# ESP_toster_2021-06-03.net
KiCad netlist of a schematic drawn in EasyEDA
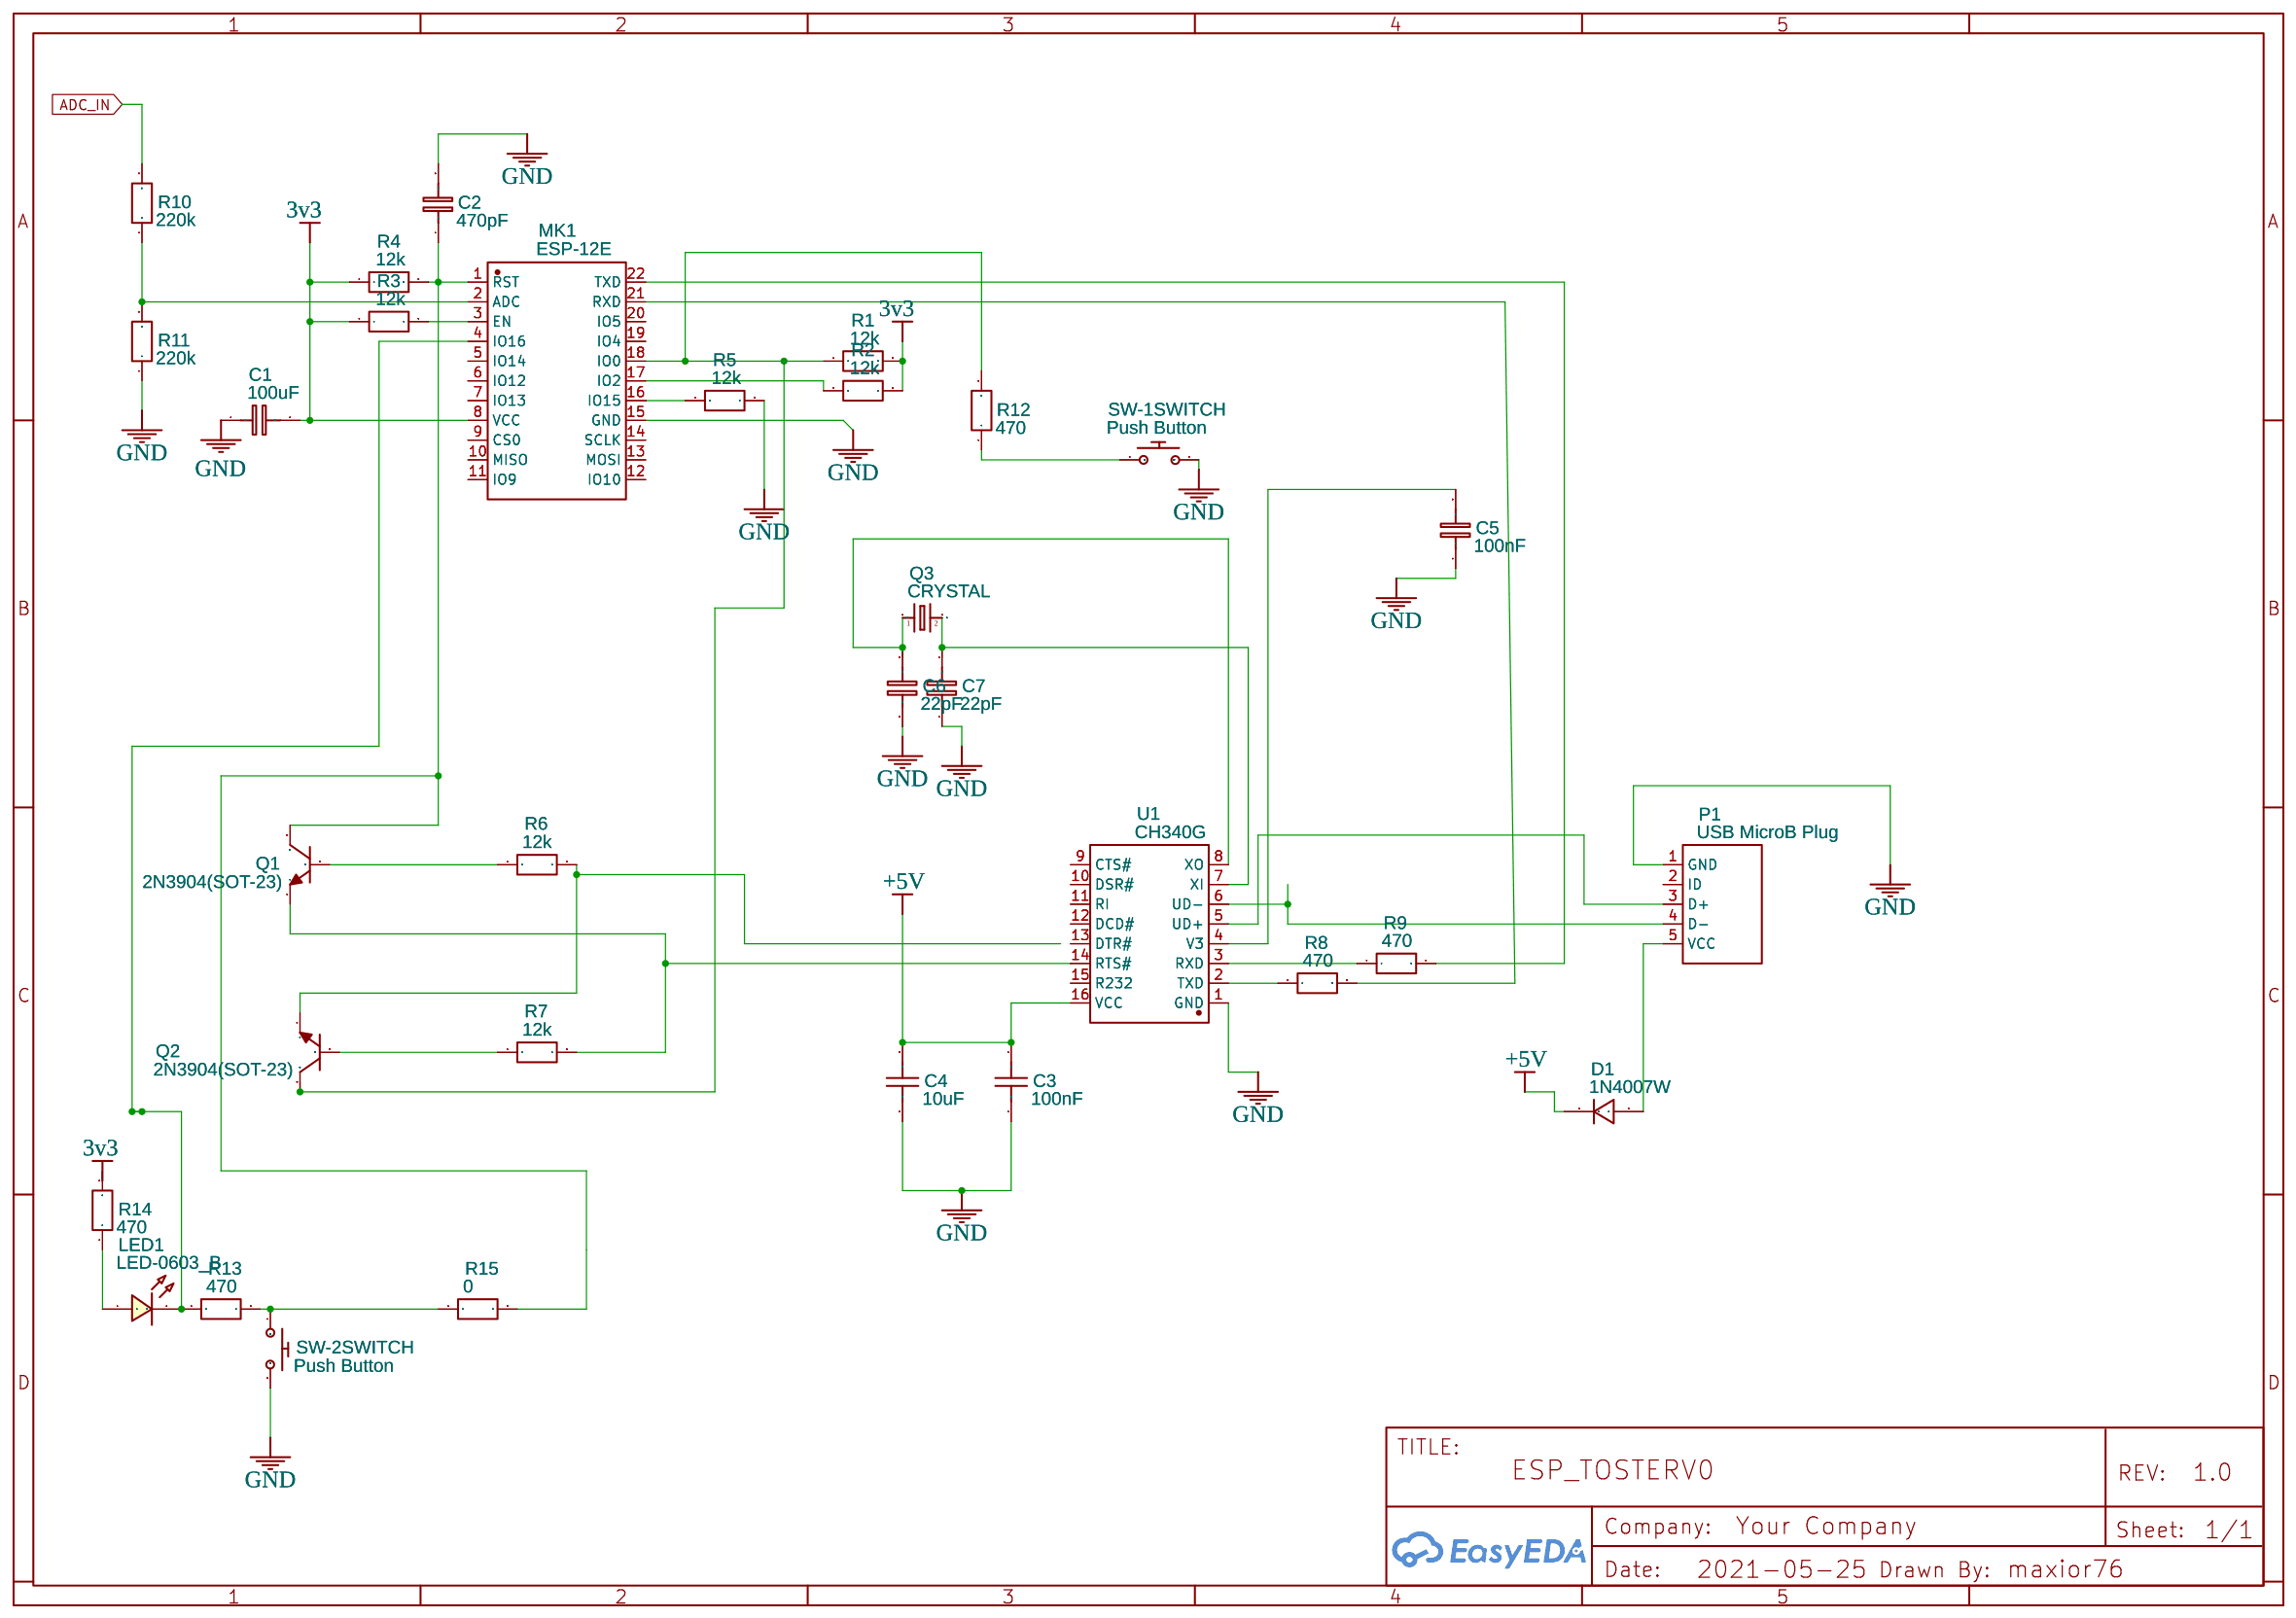
[diagram p0: schematic sheet]

(export (version "E")
  (design (tool "Eeschema 10.0.6"))
  (components
    (comp (ref "C1") (value "100uF") (libsource (lib "") (part "C_0603_EU")))
    (comp (ref "C2") (value "470pF") (libsource (lib "") (part "C_0603_EU_3")))
    (comp (ref "C3") (value "100nF") (libsource (lib "") (part "C_0603_US")))
    (comp (ref "C4") (value "10uF") (libsource (lib "") (part "C_0603_US")))
    (comp (ref "C5") (value "100nF") (libsource (lib "") (part "C_0603_EU_1")))
    (comp (ref "C6") (value "22pF") (libsource (lib "") (part "C_0603_EU_2")))
    (comp (ref "C7") (value "22pF") (libsource (lib "") (part "C_0603_EU_2")))
    (comp (ref "D1")
      (value "1N4007W")
      (fields (field (name "BOM_Supplier Part") "C328592"))
      (libsource (lib "") (part "1N4007W"))
    )
    (comp (ref "LED1")
      (value "LED-0603_B")
      (fields
        (field (name "BOM_Manufacturer Part") "19-217/R6C-AL1M2VY/3T")
        (field (name "BOM_Supplier Part") "C72044")
      )
      (libsource (lib "") (part "LED-0603_R"))
    )
    (comp (ref "MK1")
      (value "ESP-12E")
      (fields (field (name "BOM_Supplier Part") "C89297"))
      (libsource (lib "") (part "ESP-12E"))
    )
    (comp (ref "P1") (value "USB MicroB Plug") (libsource (lib "") (part "USB MicroB Plug")))
    (comp (ref "Q1")
      (value "2N3904(SOT-23)")
      (fields
        (field (name "BOM_Manufacturer Part") "2n3904S-RTK/PS")
        (field (name "BOM_Supplier Part") "C18536")
      )
      (libsource (lib "") (part "2N3904(SOT-23)_1"))
    )
    (comp (ref "Q2")
      (value "2N3904(SOT-23)")
      (fields
        (field (name "BOM_Manufacturer Part") "2n3904S-RTK/PS")
        (field (name "BOM_Supplier Part") "C18536")
      )
      (libsource (lib "") (part "2N3904(SOT-23)"))
    )
    (comp (ref "Q3") (value "CRYSTAL") (libsource (lib "") (part "CRYSTAL")))
    (comp (ref "R1") (value "12k") (libsource (lib "") (part "R_0603_EU")))
    (comp (ref "R2") (value "12k") (libsource (lib "") (part "R_0603_EU")))
    (comp (ref "R3") (value "12k") (libsource (lib "") (part "R_0603_EU")))
    (comp (ref "R4") (value "12k") (libsource (lib "") (part "R_0603_EU")))
    (comp (ref "R5") (value "12k") (libsource (lib "") (part "R_0603_EU")))
    (comp (ref "R6") (value "12k") (libsource (lib "") (part "R_0603_EU")))
    (comp (ref "R7") (value "12k") (libsource (lib "") (part "R_0603_EU")))
    (comp (ref "R8") (value "470") (libsource (lib "") (part "R_0603_EU")))
    (comp (ref "R9") (value "470") (libsource (lib "") (part "R_0603_EU")))
    (comp (ref "R10") (value "220k") (libsource (lib "") (part "R_0603_EU_1")))
    (comp (ref "R11") (value "220k") (libsource (lib "") (part "R_0603_EU_1")))
    (comp (ref "R12") (value "470") (libsource (lib "") (part "R_0603_EU_1")))
    (comp (ref "R13") (value "470") (libsource (lib "") (part "R_0603_EU")))
    (comp (ref "R14") (value "470") (libsource (lib "") (part "R_0603_EU_1")))
    (comp (ref "R15") (value "0") (libsource (lib "") (part "R_0603_EU")))
    (comp (ref "SW-1SWITCH")
      (value "Push Button")
      (fields (field (name "BOM_Supplier Part") "COM-08720"))
      (libsource (lib "") (part "Push Button_1"))
    )
    (comp (ref "SW-2SWITCH")
      (value "Push Button")
      (fields (field (name "BOM_Supplier Part") "COM-08720"))
      (libsource (lib "") (part "Push Button"))
    )
    (comp (ref "U1")
      (value "CH340G")
      (fields (field (name "BOM_Supplier Part") "C14267"))
      (libsource (lib "") (part "CH340G"))
    )
  )
  (nets
    (net (code "1") (name "+5V") (class "Default")
      (node (ref "C3") (pin "2") (pinfunction "2_2") (pintype "unspecified"))
      (node (ref "C4") (pin "2") (pinfunction "2_2") (pintype "unspecified"))
      (node (ref "D1") (pin "1") (pinfunction "1_1") (pintype "unspecified"))
      (node (ref "U1") (pin "16") (pinfunction "VCC_16") (pintype "unspecified"))
    )
    (net (code "2") (name "3v3") (class "Default")
      (node (ref "C1") (pin "2") (pinfunction "2_2") (pintype "unspecified"))
      (node (ref "MK1") (pin "8") (pinfunction "VCC_8") (pintype "unspecified"))
      (node (ref "R1") (pin "2") (pinfunction "2_2") (pintype "unspecified"))
      (node (ref "R14") (pin "2") (pinfunction "2_2") (pintype "unspecified"))
      (node (ref "R2") (pin "2") (pinfunction "2_2") (pintype "unspecified"))
      (node (ref "R3") (pin "1") (pinfunction "1_1") (pintype "unspecified"))
      (node (ref "R4") (pin "1") (pinfunction "1_1") (pintype "unspecified"))
    )
    (net (code "3") (name "ADC_IN") (class "Default")
      (node (ref "R10") (pin "2") (pinfunction "2_2") (pintype "unspecified"))
    )
    (net (code "4") (name "GND") (class "Default")
      (node (ref "C1") (pin "1") (pinfunction "1_1") (pintype "unspecified"))
      (node (ref "C2") (pin "2") (pinfunction "2_2") (pintype "unspecified"))
      (node (ref "C3") (pin "1") (pinfunction "1_1") (pintype "unspecified"))
      (node (ref "C4") (pin "1") (pinfunction "1_1") (pintype "unspecified"))
      (node (ref "C5") (pin "1") (pinfunction "1_1") (pintype "unspecified"))
      (node (ref "C6") (pin "1") (pinfunction "1_1") (pintype "unspecified"))
      (node (ref "C7") (pin "1") (pinfunction "1_1") (pintype "unspecified"))
      (node (ref "MK1") (pin "15") (pinfunction "GND_15") (pintype "unspecified"))
      (node (ref "P1") (pin "1") (pinfunction "GND_1") (pintype "unspecified"))
      (node (ref "R11") (pin "1") (pinfunction "1_1") (pintype "unspecified"))
      (node (ref "R5") (pin "2") (pinfunction "2_2") (pintype "unspecified"))
      (node (ref "SW-1SWITCH") (pin "2") (pinfunction "P$2_2") (pintype "unspecified"))
      (node (ref "SW-2SWITCH") (pin "2") (pinfunction "P$2_2") (pintype "unspecified"))
      (node (ref "U1") (pin "1") (pinfunction "GND_1") (pintype "unspecified"))
    )
    (net (code "5") (name "Net-(LED1-Pad1)") (class "Default")
      (node (ref "LED1") (pin "1") (pinfunction "1_1") (pintype "unspecified"))
      (node (ref "R14") (pin "1") (pinfunction "1_1") (pintype "unspecified"))
    )
    (net (code "6") (name "Net-(MK1-ADC)") (class "Default")
      (node (ref "MK1") (pin "2") (pinfunction "ADC_2") (pintype "unspecified"))
      (node (ref "R10") (pin "1") (pinfunction "1_1") (pintype "unspecified"))
      (node (ref "R11") (pin "2") (pinfunction "2_2") (pintype "unspecified"))
    )
    (net (code "7") (name "Net-(MK1-EN)") (class "Default")
      (node (ref "MK1") (pin "3") (pinfunction "EN_3") (pintype "unspecified"))
      (node (ref "R3") (pin "2") (pinfunction "2_2") (pintype "unspecified"))
    )
    (net (code "8") (name "Net-(MK1-IO0)") (class "Default")
      (node (ref "MK1") (pin "18") (pinfunction "IO0_18") (pintype "unspecified"))
      (node (ref "Q2") (pin "3") (pinfunction "C_3") (pintype "input"))
      (node (ref "R1") (pin "1") (pinfunction "1_1") (pintype "unspecified"))
      (node (ref "R12") (pin "2") (pinfunction "2_2") (pintype "unspecified"))
    )
    (net (code "9") (name "Net-(MK1-IO2)") (class "Default")
      (node (ref "MK1") (pin "17") (pinfunction "IO2_17") (pintype "unspecified"))
      (node (ref "R2") (pin "1") (pinfunction "1_1") (pintype "unspecified"))
    )
    (net (code "10") (name "Net-(MK1-IO15)") (class "Default")
      (node (ref "MK1") (pin "16") (pinfunction "IO15_16") (pintype "unspecified"))
      (node (ref "R5") (pin "1") (pinfunction "1_1") (pintype "unspecified"))
    )
    (net (code "11") (name "Net-(MK1-IO16)") (class "Default")
      (node (ref "LED1") (pin "2") (pinfunction "2_2") (pintype "unspecified"))
      (node (ref "MK1") (pin "4") (pinfunction "IO16_4") (pintype "unspecified"))
      (node (ref "R13") (pin "1") (pinfunction "1_1") (pintype "unspecified"))
    )
    (net (code "12") (name "Net-(MK1-RST)") (class "Default")
      (node (ref "C2") (pin "1") (pinfunction "1_1") (pintype "unspecified"))
      (node (ref "MK1") (pin "1") (pinfunction "RST_1") (pintype "unspecified"))
      (node (ref "Q1") (pin "3") (pinfunction "C_3") (pintype "input"))
      (node (ref "R15") (pin "2") (pinfunction "2_2") (pintype "unspecified"))
      (node (ref "R4") (pin "2") (pinfunction "2_2") (pintype "unspecified"))
    )
    (net (code "13") (name "Net-(MK1-RXD)") (class "Default")
      (node (ref "MK1") (pin "21") (pinfunction "RXD_21") (pintype "unspecified"))
      (node (ref "R8") (pin "2") (pinfunction "2_2") (pintype "unspecified"))
    )
    (net (code "14") (name "Net-(MK1-TXD)") (class "Default")
      (node (ref "MK1") (pin "22") (pinfunction "TXD_22") (pintype "unspecified"))
      (node (ref "R9") (pin "2") (pinfunction "2_2") (pintype "unspecified"))
    )
    (net (code "15") (name "Net-(P1-D+)") (class "Default")
      (node (ref "P1") (pin "3") (pinfunction "D+_3") (pintype "unspecified"))
      (node (ref "U1") (pin "5") (pinfunction "UD+_5") (pintype "unspecified"))
    )
    (net (code "16") (name "Net-(P1-D-)") (class "Default")
      (node (ref "P1") (pin "4") (pinfunction "D-_4") (pintype "unspecified"))
      (node (ref "U1") (pin "6") (pinfunction "UD-_6") (pintype "unspecified"))
    )
    (net (code "17") (name "Net-(P1-VCC)") (class "Default")
      (node (ref "D1") (pin "2") (pinfunction "2_2") (pintype "unspecified"))
      (node (ref "P1") (pin "5") (pinfunction "VCC_5") (pintype "unspecified"))
    )
    (net (code "18") (name "Net-(Q1-B)") (class "Default")
      (node (ref "Q1") (pin "2") (pinfunction "B_2") (pintype "input"))
      (node (ref "R6") (pin "1") (pinfunction "1_1") (pintype "unspecified"))
    )
    (net (code "19") (name "Net-(Q1-E)") (class "Default")
      (node (ref "Q1") (pin "1") (pinfunction "E_1") (pintype "input"))
      (node (ref "R7") (pin "2") (pinfunction "2_2") (pintype "unspecified"))
      (node (ref "U1") (pin "14") (pinfunction "RTS#_14") (pintype "unspecified"))
    )
    (net (code "20") (name "Net-(Q2-B)") (class "Default")
      (node (ref "Q2") (pin "2") (pinfunction "B_2") (pintype "input"))
      (node (ref "R7") (pin "1") (pinfunction "1_1") (pintype "unspecified"))
    )
    (net (code "21") (name "Net-(Q2-E)") (class "Default")
      (node (ref "Q2") (pin "1") (pinfunction "E_1") (pintype "input"))
      (node (ref "R6") (pin "2") (pinfunction "2_2") (pintype "unspecified"))
    )
    (net (code "22") (name "Net-(SW-1SWITCH-P$1)") (class "Default")
      (node (ref "R12") (pin "1") (pinfunction "1_1") (pintype "unspecified"))
      (node (ref "SW-1SWITCH") (pin "1") (pinfunction "P$1_1") (pintype "unspecified"))
    )
    (net (code "23") (name "Net-(SW-2SWITCH-P$1)") (class "Default")
      (node (ref "R13") (pin "2") (pinfunction "2_2") (pintype "unspecified"))
      (node (ref "R15") (pin "1") (pinfunction "1_1") (pintype "unspecified"))
      (node (ref "SW-2SWITCH") (pin "1") (pinfunction "P$1_1") (pintype "unspecified"))
    )
    (net (code "24") (name "Net-(U1-RXD)") (class "Default")
      (node (ref "R9") (pin "1") (pinfunction "1_1") (pintype "unspecified"))
      (node (ref "U1") (pin "3") (pinfunction "RXD_3") (pintype "unspecified"))
    )
    (net (code "25") (name "Net-(U1-TXD)") (class "Default")
      (node (ref "R8") (pin "1") (pinfunction "1_1") (pintype "unspecified"))
      (node (ref "U1") (pin "2") (pinfunction "TXD_2") (pintype "unspecified"))
    )
    (net (code "26") (name "Net-(U1-V3)") (class "Default")
      (node (ref "C5") (pin "2") (pinfunction "2_2") (pintype "unspecified"))
      (node (ref "U1") (pin "4") (pinfunction "V3_4") (pintype "unspecified"))
    )
    (net (code "27") (name "Net-(U1-XI)") (class "Default")
      (node (ref "C7") (pin "2") (pinfunction "2_2") (pintype "unspecified"))
      (node (ref "Q3") (pin "2") (pinfunction "2_2") (pintype "unspecified"))
      (node (ref "U1") (pin "7") (pinfunction "XI_7") (pintype "unspecified"))
    )
    (net (code "28") (name "Net-(U1-XO)") (class "Default")
      (node (ref "C6") (pin "2") (pinfunction "2_2") (pintype "unspecified"))
      (node (ref "Q3") (pin "1") (pinfunction "1_1") (pintype "unspecified"))
      (node (ref "U1") (pin "8") (pinfunction "XO_8") (pintype "unspecified"))
    )
    (net (code "29") (name "unconnected-(MK1-CS0-Pad9)") (class "Default")
      (node (ref "MK1") (pin "9") (pinfunction "CS0_9") (pintype "unspecified"))
    )
    (net (code "30") (name "unconnected-(MK1-IO4-Pad19)") (class "Default")
      (node (ref "MK1") (pin "19") (pinfunction "IO4_19") (pintype "unspecified"))
    )
    (net (code "31") (name "unconnected-(MK1-IO5-Pad20)") (class "Default")
      (node (ref "MK1") (pin "20") (pinfunction "IO5_20") (pintype "unspecified"))
    )
    (net (code "32") (name "unconnected-(MK1-IO9-Pad11)") (class "Default")
      (node (ref "MK1") (pin "11") (pinfunction "IO9_11") (pintype "unspecified"))
    )
    (net (code "33") (name "unconnected-(MK1-IO10-Pad12)") (class "Default")
      (node (ref "MK1") (pin "12") (pinfunction "IO10_12") (pintype "unspecified"))
    )
    (net (code "34") (name "unconnected-(MK1-IO12-Pad6)") (class "Default")
      (node (ref "MK1") (pin "6") (pinfunction "IO12_6") (pintype "unspecified"))
    )
    (net (code "35") (name "unconnected-(MK1-IO13-Pad7)") (class "Default")
      (node (ref "MK1") (pin "7") (pinfunction "IO13_7") (pintype "unspecified"))
    )
    (net (code "36") (name "unconnected-(MK1-IO14-Pad5)") (class "Default")
      (node (ref "MK1") (pin "5") (pinfunction "IO14_5") (pintype "unspecified"))
    )
    (net (code "37") (name "unconnected-(MK1-MISO-Pad10)") (class "Default")
      (node (ref "MK1") (pin "10") (pinfunction "MISO_10") (pintype "unspecified"))
    )
    (net (code "38") (name "unconnected-(MK1-MOSI-Pad13)") (class "Default")
      (node (ref "MK1") (pin "13") (pinfunction "MOSI_13") (pintype "unspecified"))
    )
    (net (code "39") (name "unconnected-(MK1-SCLK-Pad14)") (class "Default")
      (node (ref "MK1") (pin "14") (pinfunction "SCLK_14") (pintype "unspecified"))
    )
    (net (code "40") (name "unconnected-(P1-ID-Pad2)") (class "Default")
      (node (ref "P1") (pin "2") (pinfunction "ID_2") (pintype "unspecified"))
    )
    (net (code "41") (name "unconnected-(U1-CTS#-Pad9)") (class "Default")
      (node (ref "U1") (pin "9") (pinfunction "CTS#_9") (pintype "unspecified"))
    )
    (net (code "42") (name "unconnected-(U1-DCD#-Pad12)") (class "Default")
      (node (ref "U1") (pin "12") (pinfunction "DCD#_12") (pintype "unspecified"))
    )
    (net (code "43") (name "unconnected-(U1-DSR#-Pad10)") (class "Default")
      (node (ref "U1") (pin "10") (pinfunction "DSR#_10") (pintype "unspecified"))
    )
    (net (code "44") (name "unconnected-(U1-DTR#-Pad13)") (class "Default")
      (node (ref "U1") (pin "13") (pinfunction "DTR#_13") (pintype "unspecified"))
    )
    (net (code "45") (name "unconnected-(U1-R232-Pad15)") (class "Default")
      (node (ref "U1") (pin "15") (pinfunction "R232_15") (pintype "unspecified"))
    )
    (net (code "46") (name "unconnected-(U1-RI-Pad11)") (class "Default")
      (node (ref "U1") (pin "11") (pinfunction "RI_11") (pintype "unspecified"))
    )
  )
)
